# Channel_1.net
KiCad netlist of a schematic drawn in Altium Designer
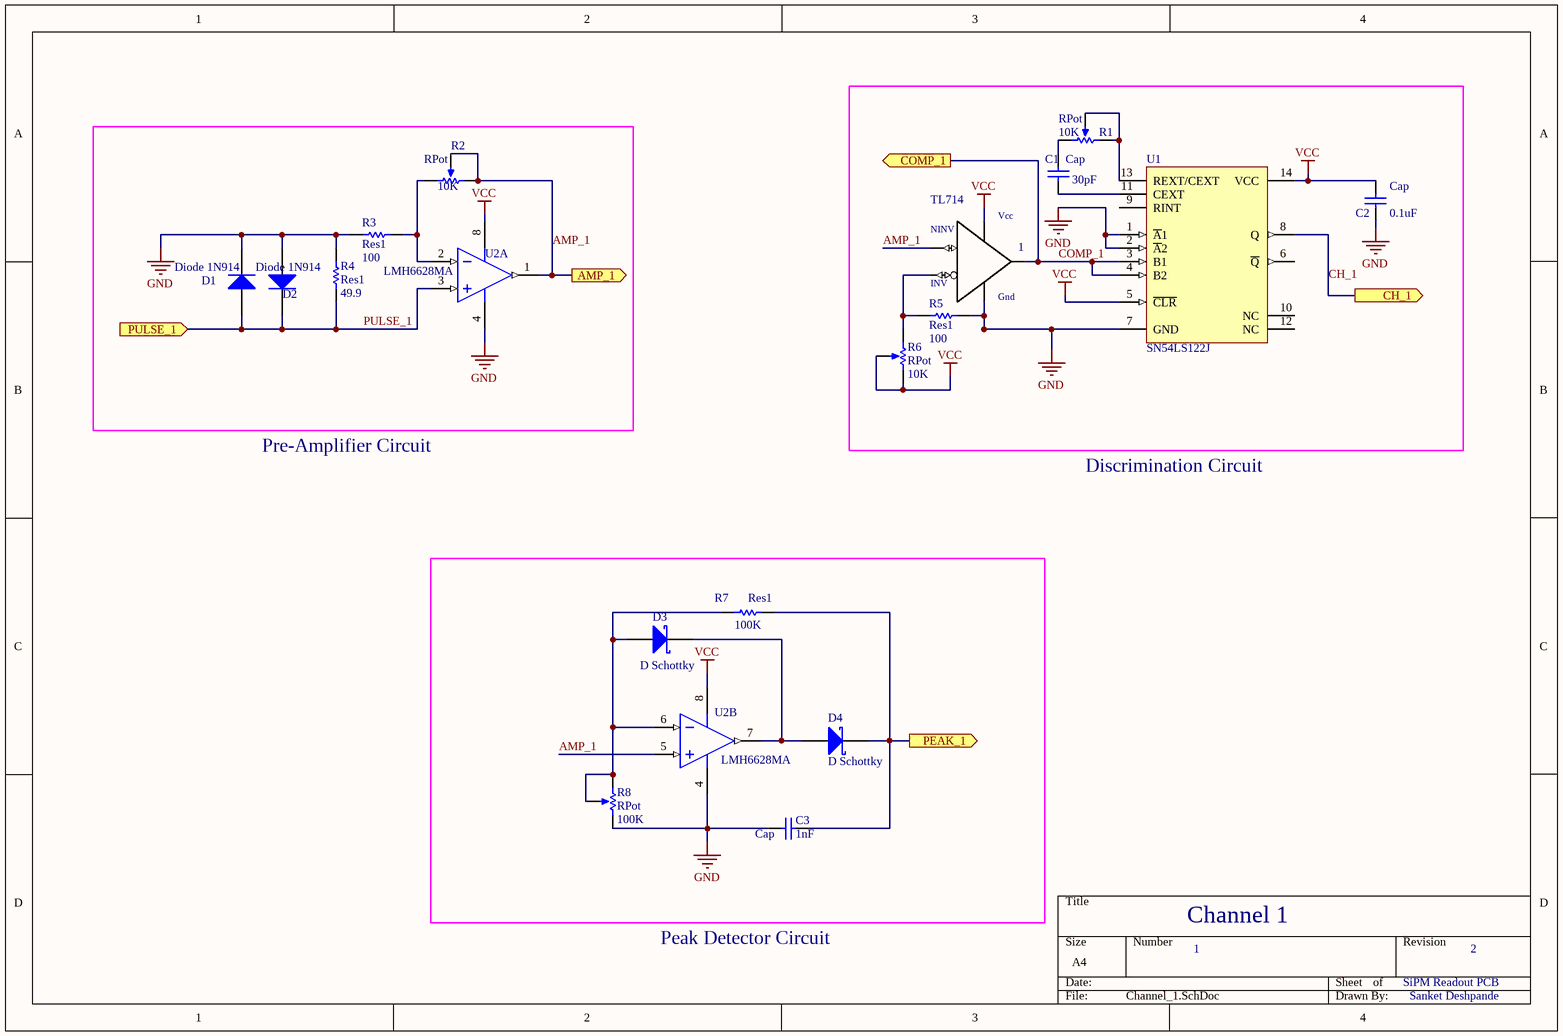
[diagram p0: Channel_1.SchDoc]

(export (version "E")
  (design (tool "Eeschema 10.0.6"))
  (components
    (comp (ref "1")
      (value "TL714")
      (footprint "SO-08M")
      (fields (field (name "MF") "Texas Instruments"))
      (libsource (lib "TL714") (part "TL714"))
    )
    (comp (ref "C1")
      (value "Cap")
      (footprint "RAD-0.3")
      (description "Capacitor")
      (fields (field (name "ALTIUM_VALUE") "30pF") (field (name "PUBLISHER") "Altium Limited"))
      (libsource (lib "Miscellaneous Devices") (part "Cap"))
    )
    (comp (ref "C2")
      (value "Cap")
      (footprint "RAD-0.3")
      (description "Capacitor")
      (fields (field (name "ALTIUM_VALUE") "0.1uF") (field (name "PUBLISHER") "Altium Limited"))
      (libsource (lib "Miscellaneous Devices") (part "Cap"))
    )
    (comp (ref "C3")
      (value "Cap")
      (footprint "RAD-0.3")
      (description "Capacitor")
      (fields (field (name "ALTIUM_VALUE") "1nF") (field (name "PUBLISHER") "Altium Limited"))
      (libsource (lib "Miscellaneous Devices") (part "Cap"))
    )
    (comp (ref "D1")
      (value "Diode 1N914")
      (footprint "DO-35")
      (description "High Conductance Fast Diode")
      (fields (field (name "PUBLISHER") "Altium Limited"))
      (libsource (lib "Miscellaneous Devices") (part "Diode 1N914"))
    )
    (comp (ref "D2")
      (value "Diode 1N914")
      (footprint "DO-35")
      (description "High Conductance Fast Diode")
      (fields (field (name "PUBLISHER") "Altium Limited"))
      (libsource (lib "Miscellaneous Devices") (part "Diode 1N914"))
    )
    (comp (ref "D3")
      (value "D Schottky")
      (footprint "SMB")
      (description "Schottky Diode")
      (fields (field (name "PUBLISHER") "Altium Limited"))
      (libsource (lib "Miscellaneous Devices") (part "D Schottky"))
    )
    (comp (ref "D4")
      (value "D Schottky")
      (footprint "SMB")
      (description "Schottky Diode")
      (fields (field (name "PUBLISHER") "Altium Limited"))
      (libsource (lib "Miscellaneous Devices") (part "D Schottky"))
    )
    (comp (ref "R1")
      (value "RPot")
      (footprint "VR5")
      (description "Potentiometer")
      (fields (field (name "ALTIUM_VALUE") "10K") (field (name "PUBLISHER") "Altium Limited"))
      (libsource (lib "Miscellaneous Devices") (part "RPot"))
    )
    (comp (ref "R2")
      (value "RPot")
      (footprint "VR5")
      (description "Potentiometer")
      (fields (field (name "ALTIUM_VALUE") "10K") (field (name "PUBLISHER") "Altium Limited"))
      (libsource (lib "Miscellaneous Devices") (part "RPot"))
    )
    (comp (ref "R3")
      (value "Res1")
      (footprint "AXIAL-0.3")
      (description "Resistor")
      (fields (field (name "ALTIUM_VALUE") "100") (field (name "PUBLISHER") "Altium Limited"))
      (libsource (lib "Miscellaneous Devices") (part "Res1"))
    )
    (comp (ref "R4")
      (value "Res1")
      (footprint "AXIAL-0.3")
      (description "Resistor")
      (fields (field (name "ALTIUM_VALUE") "49.9") (field (name "PUBLISHER") "Altium Limited"))
      (libsource (lib "Miscellaneous Devices") (part "Res1"))
    )
    (comp (ref "R5")
      (value "Res1")
      (footprint "AXIAL-0.3")
      (description "Resistor")
      (fields (field (name "ALTIUM_VALUE") "100") (field (name "PUBLISHER") "Altium Limited"))
      (libsource (lib "Miscellaneous Devices") (part "Res1"))
    )
    (comp (ref "R6")
      (value "RPot")
      (footprint "VR5")
      (description "Potentiometer")
      (fields (field (name "ALTIUM_VALUE") "10K") (field (name "PUBLISHER") "Altium Limited"))
      (libsource (lib "Miscellaneous Devices") (part "RPot"))
    )
    (comp (ref "R7")
      (value "Res1")
      (footprint "AXIAL-0.3")
      (description "Resistor")
      (fields (field (name "ALTIUM_VALUE") "100K") (field (name "PUBLISHER") "Altium Limited"))
      (libsource (lib "Miscellaneous Devices") (part "Res1"))
    )
    (comp (ref "R8")
      (value "RPot")
      (footprint "VR5")
      (description "Potentiometer")
      (fields (field (name "ALTIUM_VALUE") "100K") (field (name "PUBLISHER") "Altium Limited"))
      (libsource (lib "Miscellaneous Devices") (part "RPot"))
    )
    (comp (ref "U1")
      (value "SN54LS122J")
      (footprint "J014")
      (description "Retriggerable Monostable Multivibrator")
      (fields (field (name "PUBLISHER") "Altium Limited"))
      (libsource (lib "TI Logic Multivibrator") (part "SN54LS122J"))
    )
    (comp (ref "U2")
      (value "LMH6628MA")
      (footprint "M08A_N")
      (description "Dual Wideband, Low Noise, Voltage Feedback Op Amp, 8-pin Narrow SOIC")
      (fields (field (name "MANUFACTURER") "National Semiconductor"))
      (libsource (lib "National Semiconductor Amplifier") (part "LMH6628MA"))
    )
  )
  (nets
    (net (code "1") (name "/AMP_1") (class "Default")
      (node (ref "1") (pin "3") (pinfunction "NINV_3") (pintype "bidirectional"))
      (node (ref "R2") (pin "1") (pinfunction "TOP_1") (pintype "passive"))
      (node (ref "R2") (pin "3") (pinfunction "TAP_3") (pintype "passive"))
      (node (ref "U2") (pin "1") (pinfunction "OUT1_1") (pintype "output"))
      (node (ref "U2") (pin "5") (pinfunction "IN2+_5") (pintype "input"))
    )
    (net (code "2") (name "/CH_1") (class "Default")
      (node (ref "U1") (pin "8") (pinfunction "Q_8") (pintype "output"))
    )
    (net (code "3") (name "/COMP_1") (class "Default")
      (node (ref "1") (pin "6") (pinfunction "OUT_6") (pintype "bidirectional"))
      (node (ref "U1") (pin "3") (pinfunction "B1_3") (pintype "input"))
      (node (ref "U1") (pin "4") (pinfunction "B2_4") (pintype "input"))
    )
    (net (code "4") (name "/PEAK_1") (class "Default")
      (node (ref "C3") (pin "2") (pinfunction "2_2") (pintype "passive"))
      (node (ref "D4") (pin "2") (pinfunction "K_2") (pintype "passive"))
      (node (ref "R7") (pin "2") (pinfunction "2_2") (pintype "passive"))
    )
    (net (code "5") (name "/PULSE_1") (class "Default")
      (node (ref "D1") (pin "1") (pinfunction "A_1") (pintype "passive"))
      (node (ref "D2") (pin "2") (pinfunction "K_2") (pintype "passive"))
      (node (ref "R4") (pin "2") (pinfunction "2_2") (pintype "passive"))
      (node (ref "U2") (pin "3") (pinfunction "IN1+_3") (pintype "input"))
    )
    (net (code "6") (name "GND") (class "Default")
      (node (ref "1") (pin "5") (pinfunction "VNEG_5") (pintype "bidirectional"))
      (node (ref "C2") (pin "1") (pinfunction "1_1") (pintype "passive"))
      (node (ref "C3") (pin "1") (pinfunction "1_1") (pintype "passive"))
      (node (ref "D1") (pin "2") (pinfunction "K_2") (pintype "passive"))
      (node (ref "D2") (pin "1") (pinfunction "A_1") (pintype "passive"))
      (node (ref "R3") (pin "1") (pinfunction "1_1") (pintype "passive"))
      (node (ref "R4") (pin "1") (pinfunction "1_1") (pintype "passive"))
      (node (ref "R5") (pin "2") (pinfunction "2_2") (pintype "passive"))
      (node (ref "R8") (pin "2") (pinfunction "BOT_2") (pintype "passive"))
      (node (ref "U1") (pin "1") (pinfunction "~{A}1_1") (pintype "input"))
      (node (ref "U1") (pin "2") (pinfunction "~{A}2_2") (pintype "input"))
      (node (ref "U1") (pin "7") (pinfunction "GND_7") (pintype "power_in"))
      (node (ref "U2") (pin "4") (pinfunction "V-_4") (pintype "power_in"))
    )
    (net (code "7") (name "Net-(1-INV)") (class "Default")
      (node (ref "1") (pin "2") (pinfunction "INV_2") (pintype "bidirectional"))
      (node (ref "R5") (pin "1") (pinfunction "1_1") (pintype "passive"))
      (node (ref "R6") (pin "1") (pinfunction "TOP_1") (pintype "passive"))
    )
    (net (code "8") (name "Net-(D3-A)") (class "Default")
      (node (ref "D3") (pin "1") (pinfunction "A_1") (pintype "passive"))
      (node (ref "R7") (pin "1") (pinfunction "1_1") (pintype "passive"))
      (node (ref "R8") (pin "1") (pinfunction "TOP_1") (pintype "passive"))
      (node (ref "R8") (pin "3") (pinfunction "TAP_3") (pintype "passive"))
      (node (ref "U2") (pin "6") (pinfunction "IN2-_6") (pintype "input"))
    )
    (net (code "9") (name "Net-(D3-K)") (class "Default")
      (node (ref "D3") (pin "2") (pinfunction "K_2") (pintype "passive"))
      (node (ref "D4") (pin "1") (pinfunction "A_1") (pintype "passive"))
      (node (ref "U2") (pin "7") (pinfunction "OUT2_7") (pintype "output"))
    )
    (net (code "10") (name "Net-(R1-BOT)") (class "Default")
      (node (ref "C1") (pin "2") (pinfunction "2_2") (pintype "passive"))
      (node (ref "R1") (pin "2") (pinfunction "BOT_2") (pintype "passive"))
    )
    (net (code "11") (name "Net-(R1-TAP)") (class "Default")
      (node (ref "R1") (pin "1") (pinfunction "TOP_1") (pintype "passive"))
      (node (ref "R1") (pin "3") (pinfunction "TAP_3") (pintype "passive"))
      (node (ref "U1") (pin "13") (pinfunction "REXT/CEXT_13") (pintype "passive"))
    )
    (net (code "12") (name "Net-(R2-BOT)") (class "Default")
      (node (ref "R2") (pin "2") (pinfunction "BOT_2") (pintype "passive"))
      (node (ref "R3") (pin "2") (pinfunction "2_2") (pintype "passive"))
      (node (ref "U2") (pin "2") (pinfunction "IN1-_2") (pintype "input"))
    )
    (net (code "13") (name "Net-(U1-CEXT)") (class "Default")
      (node (ref "C1") (pin "1") (pinfunction "1_1") (pintype "passive"))
      (node (ref "U1") (pin "11") (pinfunction "CEXT_11") (pintype "passive"))
    )
    (net (code "14") (name "VCC") (class "Default")
      (node (ref "1") (pin "8") (pinfunction "VPOS_8") (pintype "bidirectional"))
      (node (ref "C2") (pin "2") (pinfunction "2_2") (pintype "passive"))
      (node (ref "R6") (pin "2") (pinfunction "BOT_2") (pintype "passive"))
      (node (ref "R6") (pin "3") (pinfunction "TAP_3") (pintype "passive"))
      (node (ref "U1") (pin "14") (pinfunction "VCC_14") (pintype "power_in"))
      (node (ref "U1") (pin "5") (pinfunction "~{CLR}_5") (pintype "input"))
      (node (ref "U2") (pin "8") (pinfunction "V+_8") (pintype "power_in"))
    )
    (net (code "15") (name "unconnected-(U1-NC-Pad10)") (class "Default")
      (node (ref "U1") (pin "10") (pinfunction "NC_10") (pintype "passive"))
    )
    (net (code "16") (name "unconnected-(U1-NC-Pad12)") (class "Default")
      (node (ref "U1") (pin "12") (pinfunction "NC_12") (pintype "passive"))
    )
    (net (code "17") (name "unconnected-(U1-RINT-Pad9)") (class "Default")
      (node (ref "U1") (pin "9") (pinfunction "RINT_9") (pintype "passive"))
    )
    (net (code "18") (name "unconnected-(U1-~{Q}-Pad6)") (class "Default")
      (node (ref "U1") (pin "6") (pinfunction "~{Q}_6") (pintype "output"))
    )
  )
)
